# Processor.net
KiCad netlist of a schematic drawn in Altium Designer
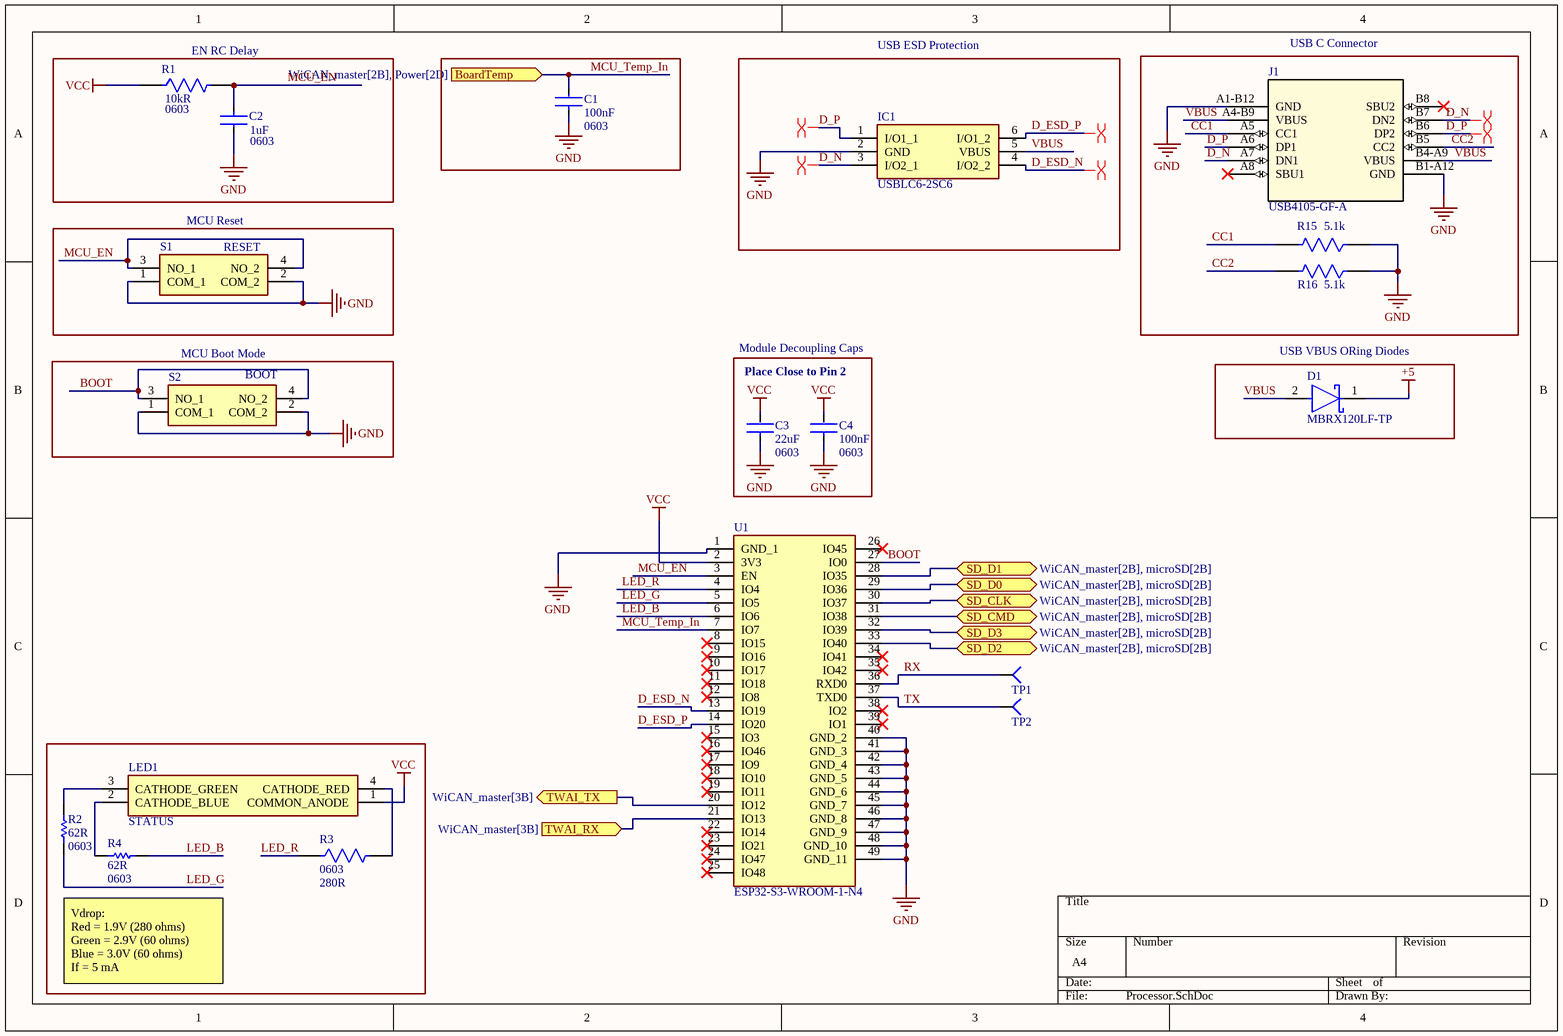
[diagram p0: Processor.SchDoc]

(export (version "E")
  (design (tool "Eeschema 10.0.6"))
  (components
    (comp (ref "C1")
      (value "CL10B104KB8WPNC")
      (footprint "FP-CL10-IPC_A")
      (description "Cap Ceramic 100nF 50V X7R ±10% Pad SMD 0603 +125°C T/R")
      (fields
        (field (name "CAPACITANCE") "100nF")
        (field (name "CASE/PACKAGE") "0603")
        (field (name "TOLERANCE") "10%")
      )
      (libsource (lib "Altium Content Vault") (part "b4654b650e69147ec39a6b967a45e02"))
    )
    (comp (ref "C2")
      (value "UMK107BJ105KA-T")
      (footprint "FP-0603-L_1_6_0_1-W_0_8_0-IPC_A")
      (description "None")
      (fields
        (field (name "TOLERANCE") "10%")
        (field (name "CASE/PACKAGE") "0603")
        (field (name "CAPACITANCE") "1uF")
      )
      (libsource (lib "Altium Content Vault") (part "02cd4be3c70576c341d710602a673aa"))
    )
    (comp (ref "C3")
      (value "GRM188R61A226ME15D")
      (footprint "FP-GRM188-0_2-IPC_C")
      (description "Chip Multilayer Ceramic Capacitors for General Purpose, 0603, 22uF, X5R, 15%, 20%, 10V")
      (fields
        (field (name "TOLERANCE") "20%")
        (field (name "CAPACITANCE") "22uF")
        (field (name "CASE CODE (IMPERIAL)") "0603")
      )
      (libsource (lib "Altium Content Vault") (part "11868f565c42a9108669ba33697ecf6"))
    )
    (comp (ref "C4")
      (value "CL10B104KB8WPNC")
      (footprint "FP-CL10-IPC_A")
      (description "Cap Ceramic 100nF 50V X7R ±10% Pad SMD 0603 +125°C T/R")
      (fields
        (field (name "CAPACITANCE") "100nF")
        (field (name "CASE/PACKAGE") "0603")
        (field (name "TOLERANCE") "10%")
      )
      (libsource (lib "Altium Content Vault") (part "b4654b650e69147ec39a6b967a45e02"))
    )
    (comp (ref "D1")
      (value "MBRX120LF-TP")
      (footprint "FP-SOD-123-IPC_A")
      (description "DIODE SCHOTTKY 20V 1A SOD123")
      (libsource (lib "Altium Content Vault") (part "1d6ec82d83fb6aee721767c19dac4b9"))
    )
    (comp (ref "IC1")
      (value "USBLC6-2SC6")
      (footprint "SOT95P280X145-6N")
      (description "Integrated Circuit")
      (fields (field (name "MOUSER PART NUMBER") "511-USBLC6-2SC6"))
      (libsource (lib "WiCAN_lib") (part "USBLC6-2SC6"))
    )
    (comp (ref "J1")
      (value "USB4105-GF-A")
      (footprint "USB4105_GCT")
      (description "No Description Available")
      (fields (field (name "COPYRIGHT") "Copyright (C) 2022 Ultra Librarian. All rights reserved."))
      (libsource (lib "WiCAN_lib") (part "USB4105-GF-A"))
    )
    (comp (ref "LED1")
      (value "STATUS")
      (footprint "CLMVCFKACL1D1L71BB7C3C3")
      (description "LED")
      (fields
        (field (name "MANUFACTURER_PART_NUMBER") "CLMVC-FKA-CL1D1L71BB7C3C3")
        (field (name "MOUSER PART NUMBER") "941-CLMVCFKACL1D1L71")
      )
      (libsource (lib "WiCAN_lib") (part "CLMVC-FKA-CL1D1L71BB7C3C3"))
    )
    (comp (ref "R1")
      (value "RMCF0603JG10K0")
      (footprint "FP-RMCF0603-MFG")
      (description "10kΩ ±5% 0.1W 0603 Thick Film Chip Resistor AEC-Q200 compliant")
      (fields
        (field (name "TOLERANCE") "5%")
        (field (name "CASE CODE (IMPERIAL)") "0603")
        (field (name "RESISTANCE") "10kR")
      )
      (libsource (lib "Altium Content Vault") (part "1029c3af85768c4190bb7ad29bc67b5"))
    )
    (comp (ref "R2")
      (value "ERJ-3GEYJ620V")
      (footprint "RESC1608X55X30ML15T15")
      (fields
        (field (name "MANUFACTURER") "Panasonic")
        (field (name "RESISTANCE") "62R")
        (field (name "PACKAGE") "0603")
      )
      (libsource (lib "Altium Content Vault") (part "RES"))
    )
    (comp (ref "R3")
      (value "RMCF0603FT280R")
      (footprint "FP-RMCF0603-MFG")
      (description "280Ω ±1% 0.1W 0603 Thick Film Chip Resistor AEC-Q200 compliant")
      (fields
        (field (name "CASE/PACKAGE") "0603")
        (field (name "TOLERANCE") "1%")
        (field (name "RESISTANCE") "280R")
      )
      (libsource (lib "Altium Content Vault") (part "1029c3af85768c4190bb7ad29bc67b5"))
    )
    (comp (ref "R4")
      (value "ERJ-3GEYJ620V")
      (footprint "RESC1608X55X30ML15T15")
      (fields
        (field (name "MANUFACTURER") "Panasonic")
        (field (name "RESISTANCE") "62R")
        (field (name "PACKAGE") "0603")
      )
      (libsource (lib "Altium Content Vault") (part "RES"))
    )
    (comp (ref "R15")
      (value "AC0603FR-135K1L")
      (footprint "FP-AC0603-MFG")
      (description "RES 5.1KΩ 1.00% 0.1W 0603")
      (fields (field (name "RESISTOR") "5.1k"))
      (libsource (lib "Altium Content Vault") (part "1029c3af85768c4190bb7ad29bc67b5"))
    )
    (comp (ref "R16")
      (value "AC0603FR-135K1L")
      (footprint "FP-AC0603-MFG")
      (description "RES 5.1KΩ 1.00% 0.1W 0603")
      (fields (field (name "RESISTOR") "5.1k"))
      (libsource (lib "Altium Content Vault") (part "1029c3af85768c4190bb7ad29bc67b5"))
    )
    (comp (ref "S1")
      (value "RESET")
      (footprint "PTS526SM15SMTR2LFS")
      (description "Switch")
      (fields
        (field (name "MANUFACTURER_PART_NUMBER") "PTS526 SM15 SMTR2 LFS")
        (field (name "MOUSER PART NUMBER") "611-PTS526SM15SMTR2L")
      )
      (libsource (lib "WiCAN_lib") (part "PTS526_SM15_SMTR2_LFS"))
    )
    (comp (ref "S2")
      (value "BOOT")
      (footprint "PTS526SM15SMTR2LFS")
      (description "Switch")
      (fields
        (field (name "MANUFACTURER_PART_NUMBER") "PTS526 SM15 SMTR2 LFS")
        (field (name "MOUSER PART NUMBER") "611-PTS526SM15SMTR2L")
      )
      (libsource (lib "WiCAN_lib") (part "PTS526_SM15_SMTR2_LFS"))
    )
    (comp (ref "TP1")
      (value "RX")
      (footprint "TESTPOINT_CIRCLE_1MM")
      (description "TESTPOINT 1MM CIRCLE")
      (libsource (lib "Connectors and Headers") (part "TESTPOINT_1MM_CIRCLE"))
    )
    (comp (ref "TP2")
      (value "TX")
      (footprint "TESTPOINT_CIRCLE_1MM")
      (description "TESTPOINT 1MM CIRCLE")
      (libsource (lib "Connectors and Headers") (part "TESTPOINT_1MM_CIRCLE"))
    )
    (comp (ref "U1")
      (value "ESP32-S3-WROOM-1-N4")
      (footprint "ESP32S3WROOM1N4")
      (description "Integrated Circuit")
      (fields (field (name "MOUSER PART NUMBER") "356-ESP32-S3WROOM1N4"))
      (libsource (lib "WiCAN_lib") (part "ESP32-S3-WROOM-1-N4"))
    )
  )
  (nets
    (net (code "1") (name "+5") (class "Default")
      (node (ref "D1") (pin "1") (pinfunction "C_1") (pintype "passive"))
    )
    (net (code "2") (name "/BOOT") (class "Default")
      (node (ref "S2") (pin "3") (pinfunction "NO_1_3") (pintype "passive"))
      (node (ref "S2") (pin "4") (pinfunction "NO_2_4") (pintype "passive"))
      (node (ref "U1") (pin "27") (pinfunction "IO0_27") (pintype "passive"))
    )
    (net (code "3") (name "/CC1") (class "Default")
      (node (ref "J1") (pin "A5") (pinfunction "CC1_A5") (pintype "bidirectional"))
      (node (ref "R15") (pin "2") (pinfunction "2_2") (pintype "passive"))
    )
    (net (code "4") (name "/CC2") (class "Default")
      (node (ref "J1") (pin "B5") (pinfunction "CC2_B5") (pintype "bidirectional"))
      (node (ref "R16") (pin "2") (pinfunction "2_2") (pintype "passive"))
    )
    (net (code "5") (name "/D_ESD_N") (class "Default")
      (node (ref "IC1") (pin "4") (pinfunction "I/O2_2_4") (pintype "passive"))
      (node (ref "U1") (pin "13") (pinfunction "IO19_13") (pintype "passive"))
    )
    (net (code "6") (name "/D_ESD_P") (class "Default")
      (node (ref "IC1") (pin "6") (pinfunction "I/O1_2_6") (pintype "passive"))
      (node (ref "U1") (pin "14") (pinfunction "IO20_14") (pintype "passive"))
    )
    (net (code "7") (name "/D_N") (class "Default")
      (node (ref "IC1") (pin "3") (pinfunction "I/O2_1_3") (pintype "passive"))
      (node (ref "J1") (pin "A7") (pinfunction "DN1_A7") (pintype "bidirectional"))
      (node (ref "J1") (pin "B7") (pinfunction "DN2_B7") (pintype "bidirectional"))
    )
    (net (code "8") (name "/D_P") (class "Default")
      (node (ref "IC1") (pin "1") (pinfunction "I/O1_1_1") (pintype "passive"))
      (node (ref "J1") (pin "A6") (pinfunction "DP1_A6") (pintype "bidirectional"))
      (node (ref "J1") (pin "B6") (pinfunction "DP2_B6") (pintype "bidirectional"))
    )
    (net (code "9") (name "/LED_B") (class "Default")
      (node (ref "R4") (pin "2") (pinfunction "2_2") (pintype "passive"))
      (node (ref "U1") (pin "6") (pinfunction "IO6_6") (pintype "passive"))
    )
    (net (code "10") (name "/LED_G") (class "Default")
      (node (ref "R2") (pin "2") (pinfunction "2_2") (pintype "passive"))
      (node (ref "U1") (pin "5") (pinfunction "IO5_5") (pintype "passive"))
    )
    (net (code "11") (name "/LED_R") (class "Default")
      (node (ref "R3") (pin "1") (pinfunction "1_1") (pintype "passive"))
      (node (ref "U1") (pin "4") (pinfunction "IO4_4") (pintype "passive"))
    )
    (net (code "12") (name "/MCU_EN") (class "Default")
      (node (ref "C2") (pin "1") (pinfunction "1_1") (pintype "passive"))
      (node (ref "R1") (pin "2") (pinfunction "2_2") (pintype "passive"))
      (node (ref "S1") (pin "3") (pinfunction "NO_1_3") (pintype "passive"))
      (node (ref "S1") (pin "4") (pinfunction "NO_2_4") (pintype "passive"))
      (node (ref "U1") (pin "3") (pinfunction "EN_3") (pintype "passive"))
    )
    (net (code "13") (name "/MCU_Temp_In") (class "Default")
      (node (ref "C1") (pin "2") (pinfunction "2_2") (pintype "passive"))
      (node (ref "U1") (pin "7") (pinfunction "IO7_7") (pintype "passive"))
    )
    (net (code "14") (name "/RX") (class "Default")
      (node (ref "TP1") (pin "1") (pinfunction "=value_1") (pintype "passive"))
      (node (ref "U1") (pin "36") (pinfunction "RXD0_36") (pintype "passive"))
    )
    (net (code "15") (name "/SD_CLK") (class "Default")
      (node (ref "U1") (pin "30") (pinfunction "IO37_30") (pintype "passive"))
    )
    (net (code "16") (name "/SD_CMD") (class "Default")
      (node (ref "U1") (pin "31") (pinfunction "IO38_31") (pintype "passive"))
    )
    (net (code "17") (name "/SD_D0") (class "Default")
      (node (ref "U1") (pin "29") (pinfunction "IO36_29") (pintype "passive"))
    )
    (net (code "18") (name "/SD_D1") (class "Default")
      (node (ref "U1") (pin "28") (pinfunction "IO35_28") (pintype "passive"))
    )
    (net (code "19") (name "/SD_D2") (class "Default")
      (node (ref "U1") (pin "33") (pinfunction "IO40_33") (pintype "passive"))
    )
    (net (code "20") (name "/SD_D3") (class "Default")
      (node (ref "U1") (pin "32") (pinfunction "IO39_32") (pintype "passive"))
    )
    (net (code "21") (name "/TWAI_RX") (class "Default")
      (node (ref "U1") (pin "21") (pinfunction "IO13_21") (pintype "passive"))
    )
    (net (code "22") (name "/TWAI_TX") (class "Default")
      (node (ref "U1") (pin "20") (pinfunction "IO12_20") (pintype "passive"))
    )
    (net (code "23") (name "/TX") (class "Default")
      (node (ref "TP2") (pin "1") (pinfunction "=value_1") (pintype "passive"))
      (node (ref "U1") (pin "37") (pinfunction "TXD0_37") (pintype "passive"))
    )
    (net (code "24") (name "/VBUS") (class "Default")
      (node (ref "D1") (pin "2") (pinfunction "A_2") (pintype "passive"))
      (node (ref "IC1") (pin "5") (pinfunction "VBUS_5") (pintype "passive"))
      (node (ref "J1") (pin "A4-B9") (pinfunction "VBUS_A4-B9") (pintype "power_in"))
      (node (ref "J1") (pin "B4-A9") (pinfunction "VBUS_B4-A9") (pintype "power_in"))
    )
    (net (code "25") (name "GND") (class "Default")
      (node (ref "C1") (pin "1") (pinfunction "1_1") (pintype "passive"))
      (node (ref "C2") (pin "2") (pinfunction "2_2") (pintype "passive"))
      (node (ref "C3") (pin "1") (pinfunction "1_1") (pintype "passive"))
      (node (ref "C4") (pin "1") (pinfunction "1_1") (pintype "passive"))
      (node (ref "IC1") (pin "2") (pinfunction "GND_2") (pintype "passive"))
      (node (ref "J1") (pin "A1-B12") (pinfunction "GND_A1-B12") (pintype "passive"))
      (node (ref "J1") (pin "B1-A12") (pinfunction "GND_B1-A12") (pintype "passive"))
      (node (ref "R15") (pin "1") (pinfunction "1_1") (pintype "passive"))
      (node (ref "R16") (pin "1") (pinfunction "1_1") (pintype "passive"))
      (node (ref "S1") (pin "1") (pinfunction "COM_1_1") (pintype "passive"))
      (node (ref "S1") (pin "2") (pinfunction "COM_2_2") (pintype "passive"))
      (node (ref "S2") (pin "1") (pinfunction "COM_1_1") (pintype "passive"))
      (node (ref "S2") (pin "2") (pinfunction "COM_2_2") (pintype "passive"))
      (node (ref "U1") (pin "1") (pinfunction "GND_1_1") (pintype "passive"))
      (node (ref "U1") (pin "40") (pinfunction "GND_2_40") (pintype "passive"))
      (node (ref "U1") (pin "41") (pinfunction "GND_3_41") (pintype "passive"))
      (node (ref "U1") (pin "42") (pinfunction "GND_4_42") (pintype "passive"))
      (node (ref "U1") (pin "43") (pinfunction "GND_5_43") (pintype "passive"))
      (node (ref "U1") (pin "44") (pinfunction "GND_6_44") (pintype "passive"))
      (node (ref "U1") (pin "45") (pinfunction "GND_7_45") (pintype "passive"))
      (node (ref "U1") (pin "46") (pinfunction "GND_8_46") (pintype "passive"))
      (node (ref "U1") (pin "47") (pinfunction "GND_9_47") (pintype "passive"))
      (node (ref "U1") (pin "48") (pinfunction "GND_10_48") (pintype "passive"))
      (node (ref "U1") (pin "49") (pinfunction "GND_11_49") (pintype "passive"))
    )
    (net (code "26") (name "Net-(LED1-CATHODE_BLUE)") (class "Default")
      (node (ref "LED1") (pin "2") (pinfunction "CATHODE_BLUE_2") (pintype "passive"))
      (node (ref "R4") (pin "1") (pinfunction "1_1") (pintype "passive"))
    )
    (net (code "27") (name "Net-(LED1-CATHODE_GREEN)") (class "Default")
      (node (ref "LED1") (pin "3") (pinfunction "CATHODE_GREEN_3") (pintype "passive"))
      (node (ref "R2") (pin "1") (pinfunction "1_1") (pintype "passive"))
    )
    (net (code "28") (name "Net-(LED1-CATHODE_RED)") (class "Default")
      (node (ref "LED1") (pin "4") (pinfunction "CATHODE_RED_4") (pintype "passive"))
      (node (ref "R3") (pin "2") (pinfunction "2_2") (pintype "passive"))
    )
    (net (code "29") (name "VCC") (class "Default")
      (node (ref "C3") (pin "2") (pinfunction "2_2") (pintype "passive"))
      (node (ref "C4") (pin "2") (pinfunction "2_2") (pintype "passive"))
      (node (ref "LED1") (pin "1") (pinfunction "COMMON_ANODE_1") (pintype "passive"))
      (node (ref "R1") (pin "1") (pinfunction "1_1") (pintype "passive"))
      (node (ref "U1") (pin "2") (pinfunction "3V3_2") (pintype "passive"))
    )
    (net (code "30") (name "unconnected-(J1-SBU1-PadA8)") (class "Default")
      (node (ref "J1") (pin "A8") (pinfunction "SBU1_A8") (pintype "bidirectional+no_connect"))
    )
    (net (code "31") (name "unconnected-(J1-SBU2-PadB8)") (class "Default")
      (node (ref "J1") (pin "B8") (pinfunction "SBU2_B8") (pintype "bidirectional+no_connect"))
    )
    (net (code "32") (name "unconnected-(U1-IO1-Pad39)") (class "Default")
      (node (ref "U1") (pin "39") (pinfunction "IO1_39") (pintype "passive+no_connect"))
    )
    (net (code "33") (name "unconnected-(U1-IO2-Pad38)") (class "Default")
      (node (ref "U1") (pin "38") (pinfunction "IO2_38") (pintype "passive+no_connect"))
    )
    (net (code "34") (name "unconnected-(U1-IO3-Pad15)") (class "Default")
      (node (ref "U1") (pin "15") (pinfunction "IO3_15") (pintype "passive+no_connect"))
    )
    (net (code "35") (name "unconnected-(U1-IO8-Pad12)") (class "Default")
      (node (ref "U1") (pin "12") (pinfunction "IO8_12") (pintype "passive+no_connect"))
    )
    (net (code "36") (name "unconnected-(U1-IO9-Pad17)") (class "Default")
      (node (ref "U1") (pin "17") (pinfunction "IO9_17") (pintype "passive+no_connect"))
    )
    (net (code "37") (name "unconnected-(U1-IO10-Pad18)") (class "Default")
      (node (ref "U1") (pin "18") (pinfunction "IO10_18") (pintype "passive+no_connect"))
    )
    (net (code "38") (name "unconnected-(U1-IO11-Pad19)") (class "Default")
      (node (ref "U1") (pin "19") (pinfunction "IO11_19") (pintype "passive"))
    )
    (net (code "39") (name "unconnected-(U1-IO14-Pad22)") (class "Default")
      (node (ref "U1") (pin "22") (pinfunction "IO14_22") (pintype "passive+no_connect"))
    )
    (net (code "40") (name "unconnected-(U1-IO15-Pad8)") (class "Default")
      (node (ref "U1") (pin "8") (pinfunction "IO15_8") (pintype "passive+no_connect"))
    )
    (net (code "41") (name "unconnected-(U1-IO16-Pad9)") (class "Default")
      (node (ref "U1") (pin "9") (pinfunction "IO16_9") (pintype "passive+no_connect"))
    )
    (net (code "42") (name "unconnected-(U1-IO17-Pad10)") (class "Default")
      (node (ref "U1") (pin "10") (pinfunction "IO17_10") (pintype "passive+no_connect"))
    )
    (net (code "43") (name "unconnected-(U1-IO18-Pad11)") (class "Default")
      (node (ref "U1") (pin "11") (pinfunction "IO18_11") (pintype "passive+no_connect"))
    )
    (net (code "44") (name "unconnected-(U1-IO21-Pad23)") (class "Default")
      (node (ref "U1") (pin "23") (pinfunction "IO21_23") (pintype "passive+no_connect"))
    )
    (net (code "45") (name "unconnected-(U1-IO41-Pad34)") (class "Default")
      (node (ref "U1") (pin "34") (pinfunction "IO41_34") (pintype "passive+no_connect"))
    )
    (net (code "46") (name "unconnected-(U1-IO42-Pad35)") (class "Default")
      (node (ref "U1") (pin "35") (pinfunction "IO42_35") (pintype "passive+no_connect"))
    )
    (net (code "47") (name "unconnected-(U1-IO45-Pad26)") (class "Default")
      (node (ref "U1") (pin "26") (pinfunction "IO45_26") (pintype "passive+no_connect"))
    )
    (net (code "48") (name "unconnected-(U1-IO46-Pad16)") (class "Default")
      (node (ref "U1") (pin "16") (pinfunction "IO46_16") (pintype "passive+no_connect"))
    )
    (net (code "49") (name "unconnected-(U1-IO47-Pad24)") (class "Default")
      (node (ref "U1") (pin "24") (pinfunction "IO47_24") (pintype "passive+no_connect"))
    )
    (net (code "50") (name "unconnected-(U1-IO48-Pad25)") (class "Default")
      (node (ref "U1") (pin "25") (pinfunction "IO48_25") (pintype "passive+no_connect"))
    )
  )
)
